# Led.net
KiCad netlist of a schematic drawn in Altium Designer
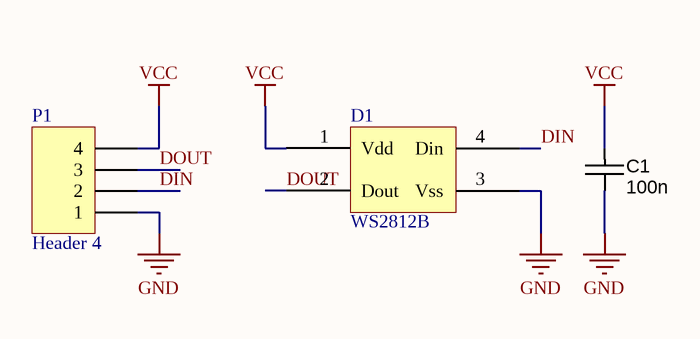
[diagram p0: Led.SchDoc]

(export (version "E")
  (design (tool "Eeschema 10.0.6"))
  (components
    (comp (ref "C1")
      (value "100n")
      (footprint "CAPC2012X135N")
      (description "Capacitor SMD Cer 100nF 10% 50V X7R 0805")
      (fields (field (name "TOLERANCE") "±10%") (field (name "Comment") "approved sub OK"))
      (libsource (lib "Library") (part "CAPC_100n_0805_X7R_50V_10%"))
    )
    (comp (ref "D1")
      (value "WS2812B")
      (footprint "5050LED")
      (description "WS2812B RGB LED")
      (libsource (lib "Library") (part "WS2812B"))
    )
    (comp (ref "P1")
      (value "Header 4")
      (footprint "HDR1X4")
      (description "Header, 4-Pin")
      (fields (field (name "PUBLISHER") "Altium Limited"))
      (libsource (lib "Miscellaneous Connectors") (part "Header 4"))
    )
  )
  (nets
    (net (code "1") (name "/DIN") (class "Default")
      (node (ref "D1") (pin "4") (pinfunction "Din_4") (pintype "passive"))
      (node (ref "P1") (pin "2") (pinfunction "2_2") (pintype "passive"))
    )
    (net (code "2") (name "/DOUT") (class "Default")
      (node (ref "D1") (pin "2") (pinfunction "Dout_2") (pintype "passive"))
      (node (ref "P1") (pin "3") (pinfunction "3_3") (pintype "passive"))
    )
    (net (code "3") (name "GND") (class "Default")
      (node (ref "C1") (pin "2") (pintype "passive"))
      (node (ref "D1") (pin "3") (pinfunction "Vss_3") (pintype "passive"))
      (node (ref "P1") (pin "1") (pinfunction "1_1") (pintype "passive"))
    )
    (net (code "4") (name "VCC") (class "Default")
      (node (ref "C1") (pin "1") (pintype "passive"))
      (node (ref "D1") (pin "1") (pinfunction "Vdd_1") (pintype "passive"))
      (node (ref "P1") (pin "4") (pinfunction "4_4") (pintype "passive"))
    )
  )
)
